# Mxxx.net
KiCad netlist of a schematic drawn in EAGLE
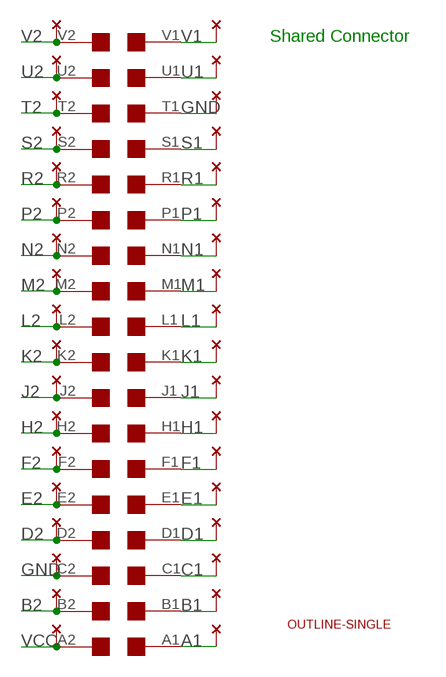
[diagram p0: schematic, sheet 1]
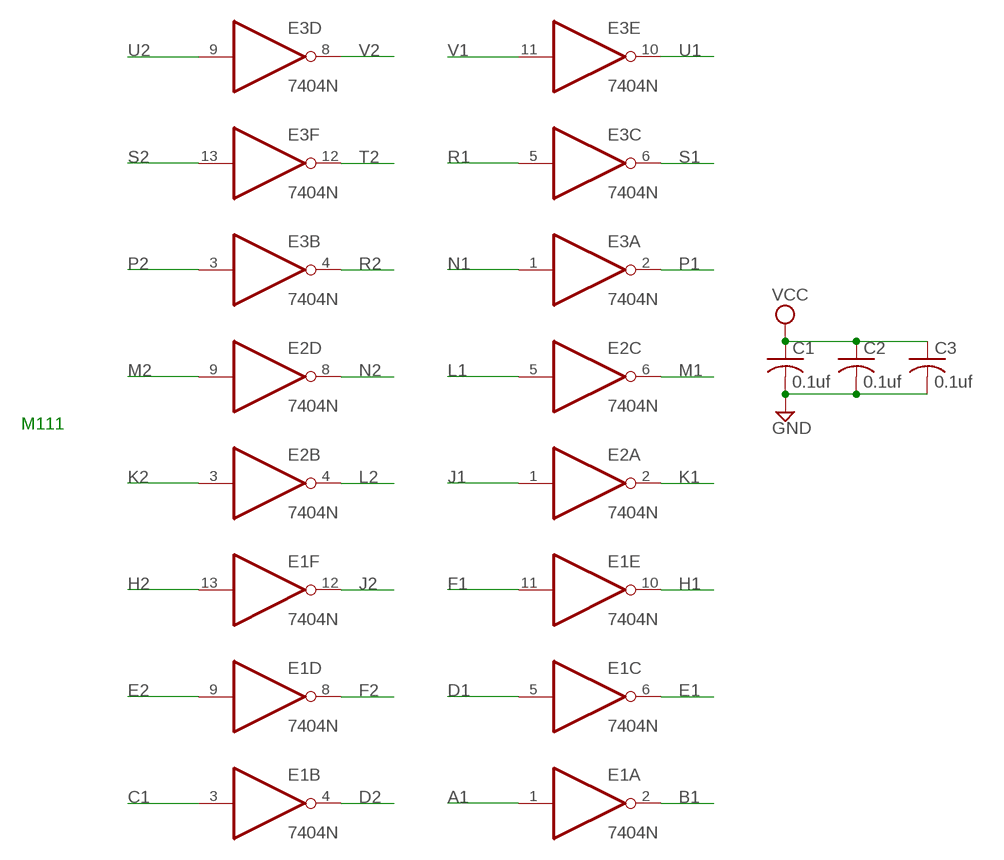
[diagram p1: schematic, sheet 2]
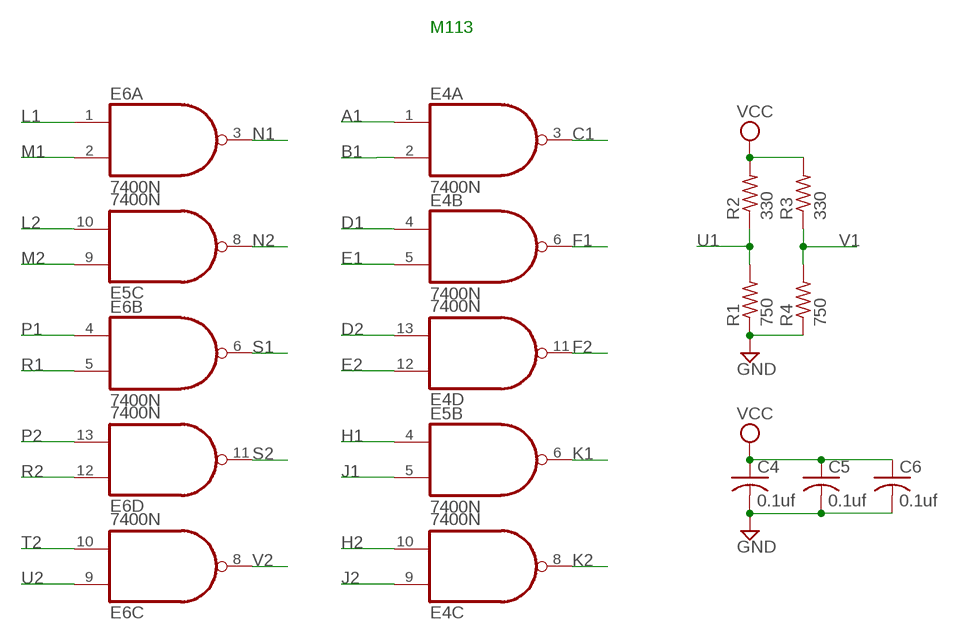
[diagram p2: schematic, sheet 3]
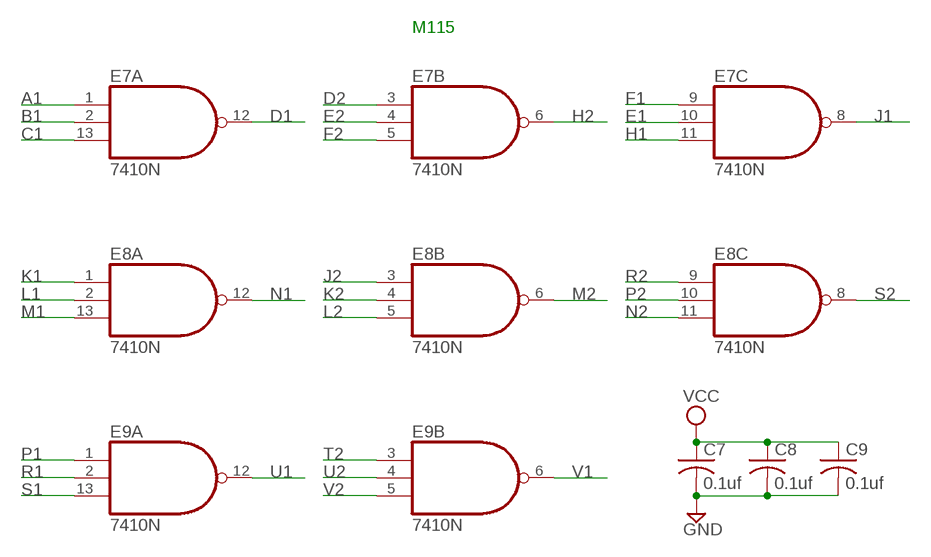
[diagram p3: schematic, sheet 4]
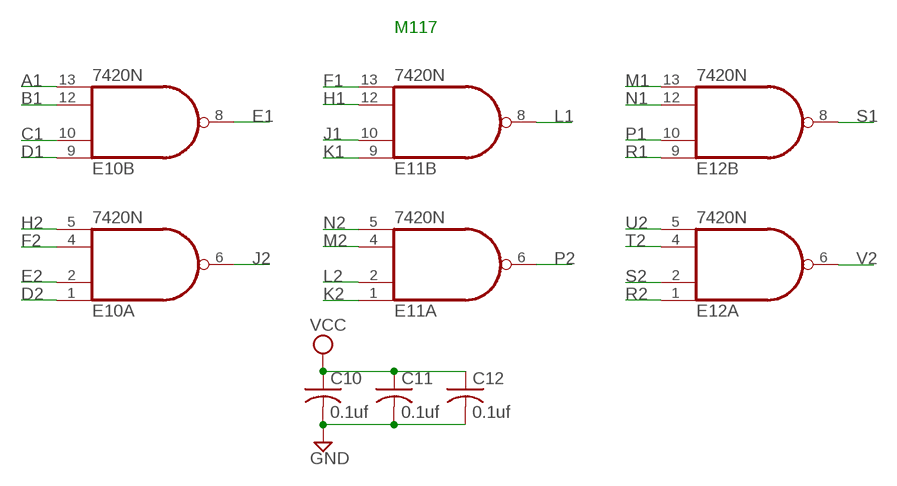
[diagram p4: schematic, sheet 5]
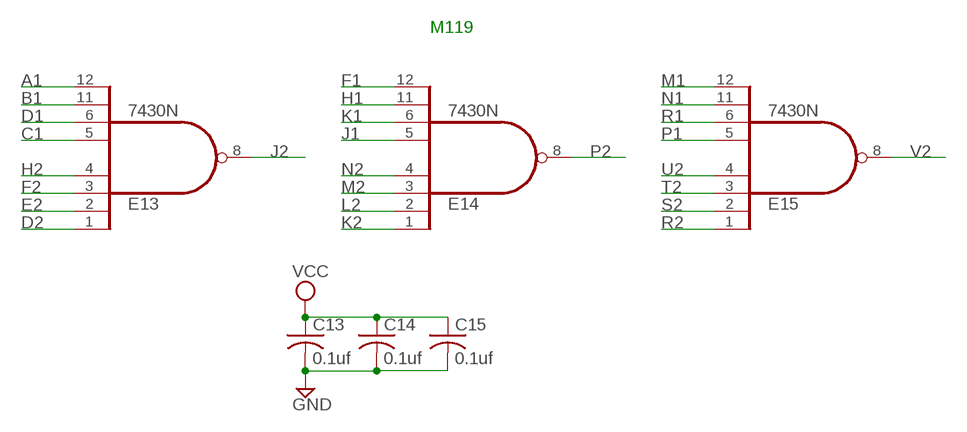
[diagram p5: schematic, sheet 6]

(export (version "E")
  (design (tool "Eeschema 10.0.6"))
  (components
    (comp (ref "C1")
      (value "0.1uf")
      (footprint "eagle-import:C050-025X075")
      (libsource (lib "eagle-import") (part "C-US050-025X075"))
    )
    (comp (ref "C2")
      (value "0.1uf")
      (footprint "eagle-import:C050-025X075")
      (libsource (lib "eagle-import") (part "C-US050-025X075"))
    )
    (comp (ref "C3")
      (value "0.1uf")
      (footprint "eagle-import:C050-025X075")
      (libsource (lib "eagle-import") (part "C-US050-025X075"))
    )
    (comp (ref "E1")
      (value "7404N")
      (footprint "eagle-import:DIL14")
      (libsource (lib "eagle-import") (part "7404N"))
    )
    (comp (ref "E2")
      (value "7404N")
      (footprint "eagle-import:DIL14")
      (libsource (lib "eagle-import") (part "7404N"))
    )
    (comp (ref "E3")
      (value "7404N")
      (footprint "eagle-import:DIL14")
      (libsource (lib "eagle-import") (part "7404N"))
    )
    (comp (ref "C13")
      (value "0.1uf")
      (footprint "eagle-import:C050-025X075")
      (libsource (lib "eagle-import") (part "C-US050-025X075"))
    )
    (comp (ref "C14")
      (value "0.1uf")
      (footprint "eagle-import:C050-025X075")
      (libsource (lib "eagle-import") (part "C-US050-025X075"))
    )
    (comp (ref "C15")
      (value "0.1uf")
      (footprint "eagle-import:C050-025X075")
      (libsource (lib "eagle-import") (part "C-US050-025X075"))
    )
    (comp (ref "E13")
      (value "7430N")
      (footprint "eagle-import:DIL14")
      (libsource (lib "eagle-import") (part "7430N"))
    )
    (comp (ref "E14")
      (value "7430N")
      (footprint "eagle-import:DIL14")
      (libsource (lib "eagle-import") (part "7430N"))
    )
    (comp (ref "E15")
      (value "7430N")
      (footprint "eagle-import:DIL14")
      (libsource (lib "eagle-import") (part "7430N"))
    )
    (comp (ref "C7")
      (value "0.1uf")
      (footprint "eagle-import:C050-025X075")
      (libsource (lib "eagle-import") (part "C-US050-025X075"))
    )
    (comp (ref "C8")
      (value "0.1uf")
      (footprint "eagle-import:C050-025X075")
      (libsource (lib "eagle-import") (part "C-US050-025X075"))
    )
    (comp (ref "C9")
      (value "0.1uf")
      (footprint "eagle-import:C050-025X075")
      (libsource (lib "eagle-import") (part "C-US050-025X075"))
    )
    (comp (ref "E7")
      (value "7410N")
      (footprint "eagle-import:DIL14")
      (libsource (lib "eagle-import") (part "7410N"))
    )
    (comp (ref "E8")
      (value "7410N")
      (footprint "eagle-import:DIL14")
      (libsource (lib "eagle-import") (part "7410N"))
    )
    (comp (ref "E9")
      (value "7410N")
      (footprint "eagle-import:DIL14")
      (libsource (lib "eagle-import") (part "7410N"))
    )
    (comp (ref "C4")
      (value "0.1uf")
      (footprint "eagle-import:C050-025X075")
      (libsource (lib "eagle-import") (part "C-US050-025X075"))
    )
    (comp (ref "C5")
      (value "0.1uf")
      (footprint "eagle-import:C050-025X075")
      (libsource (lib "eagle-import") (part "C-US050-025X075"))
    )
    (comp (ref "C6")
      (value "0.1uf")
      (footprint "eagle-import:C050-025X075")
      (libsource (lib "eagle-import") (part "C-US050-025X075"))
    )
    (comp (ref "E4")
      (value "7400N")
      (footprint "eagle-import:DIL14")
      (libsource (lib "eagle-import") (part "7400N"))
    )
    (comp (ref "E5")
      (value "7400N")
      (footprint "eagle-import:DIL14")
      (libsource (lib "eagle-import") (part "7400N"))
    )
    (comp (ref "E6")
      (value "7400N")
      (footprint "eagle-import:DIL14")
      (libsource (lib "eagle-import") (part "7400N"))
    )
    (comp (ref "R1")
      (value "750")
      (footprint "eagle-import:0207_10")
      (libsource (lib "eagle-import") (part "R-US_0207/10"))
    )
    (comp (ref "R2")
      (value "330")
      (footprint "eagle-import:0207_10")
      (libsource (lib "eagle-import") (part "R-US_0207/10"))
    )
    (comp (ref "R3")
      (value "330")
      (footprint "eagle-import:0207_10")
      (libsource (lib "eagle-import") (part "R-US_0207/10"))
    )
    (comp (ref "R4")
      (value "750")
      (footprint "eagle-import:0207_10")
      (libsource (lib "eagle-import") (part "R-US_0207/10"))
    )
    (comp (ref "C10")
      (value "0.1uf")
      (footprint "eagle-import:C050-025X075")
      (libsource (lib "eagle-import") (part "C-US050-025X075"))
    )
    (comp (ref "C11")
      (value "0.1uf")
      (footprint "eagle-import:C050-025X075")
      (libsource (lib "eagle-import") (part "C-US050-025X075"))
    )
    (comp (ref "C12")
      (value "0.1uf")
      (footprint "eagle-import:C050-025X075")
      (libsource (lib "eagle-import") (part "C-US050-025X075"))
    )
    (comp (ref "E10")
      (value "7420N")
      (footprint "eagle-import:DIL14")
      (libsource (lib "eagle-import") (part "7420NS"))
    )
    (comp (ref "E11")
      (value "7420N")
      (footprint "eagle-import:DIL14")
      (libsource (lib "eagle-import") (part "7420NS"))
    )
    (comp (ref "E12")
      (value "7420N")
      (footprint "eagle-import:DIL14")
      (libsource (lib "eagle-import") (part "7420NS"))
    )
    (comp (ref "U$1")
      (value "EDGE-2CONNECTOR")
      (footprint "eagle-import:EDGE-CON2")
      (libsource (lib "eagle-import") (part "EDGE-2CONNECTOR"))
    )
    (comp (ref "U$4")
      (value "THRU-HOLE2A")
      (footprint "eagle-import:THRU-HOLEA")
      (libsource (lib "eagle-import") (part "THRU-HOLE2A"))
    )
    (comp (ref "U$5")
      (value "OUTLINE-SINGLE")
      (footprint "eagle-import:SINGLE")
      (libsource (lib "eagle-import") (part "OUTLINE-SINGLE"))
    )
  )
  (nets
    (net (code "1") (name "A1") (class "Default")
      (node (ref "E1") (pin "1") (pinfunction "I_1") (pintype "input"))
      (node (ref "E10") (pin "13") (pinfunction "I3_13") (pintype "input"))
      (node (ref "E13") (pin "12") (pinfunction "I7_12") (pintype "input"))
      (node (ref "E4") (pin "1") (pinfunction "I0_1") (pintype "input"))
      (node (ref "E7") (pin "1") (pinfunction "I0_1") (pintype "input"))
      (node (ref "U$1") (pin "A1") (pinfunction "1_A1") (pintype "bidirectional"))
      (node (ref "U$4") (pin "A1") (pinfunction "P$1_A1") (pintype "passive"))
    )
    (net (code "2") (name "B1") (class "Default")
      (node (ref "E1") (pin "2") (pinfunction "O_2") (pintype "output"))
      (node (ref "E10") (pin "12") (pinfunction "I2_12") (pintype "input"))
      (node (ref "E13") (pin "11") (pinfunction "I6_11") (pintype "input"))
      (node (ref "E4") (pin "2") (pinfunction "I1_2") (pintype "input"))
      (node (ref "E7") (pin "2") (pinfunction "I1_2") (pintype "input"))
      (node (ref "U$1") (pin "B1") (pinfunction "1_B1") (pintype "bidirectional"))
      (node (ref "U$4") (pin "B1") (pinfunction "P$1_B1") (pintype "passive"))
    )
    (net (code "3") (name "B2") (class "Default")
      (node (ref "U$1") (pin "B2") (pinfunction "1_B2") (pintype "bidirectional"))
      (node (ref "U$4") (pin "B2") (pinfunction "P$1_B2") (pintype "passive"))
    )
    (net (code "4") (name "C1") (class "Default")
      (node (ref "E1") (pin "3") (pinfunction "I_3") (pintype "input"))
      (node (ref "E10") (pin "10") (pinfunction "I1_10") (pintype "input"))
      (node (ref "E13") (pin "5") (pinfunction "I4_5") (pintype "input"))
      (node (ref "E4") (pin "3") (pinfunction "O_3") (pintype "output"))
      (node (ref "E7") (pin "13") (pinfunction "I2_13") (pintype "input"))
      (node (ref "U$1") (pin "C1") (pinfunction "1_C1") (pintype "bidirectional"))
      (node (ref "U$4") (pin "C1") (pinfunction "P$1_C1") (pintype "passive"))
    )
    (net (code "5") (name "D1") (class "Default")
      (node (ref "E1") (pin "5") (pinfunction "I_5") (pintype "input"))
      (node (ref "E10") (pin "9") (pinfunction "I0_9") (pintype "input"))
      (node (ref "E13") (pin "6") (pinfunction "I5_6") (pintype "input"))
      (node (ref "E4") (pin "4") (pinfunction "I0_4") (pintype "input"))
      (node (ref "E7") (pin "12") (pinfunction "O_12") (pintype "output"))
      (node (ref "U$1") (pin "D1") (pinfunction "1_D1") (pintype "bidirectional"))
      (node (ref "U$4") (pin "D1") (pinfunction "P$1_D1") (pintype "passive"))
    )
    (net (code "6") (name "D2") (class "Default")
      (node (ref "E1") (pin "4") (pinfunction "O_4") (pintype "output"))
      (node (ref "E10") (pin "1") (pinfunction "I0_1") (pintype "input"))
      (node (ref "E13") (pin "1") (pinfunction "I0_1") (pintype "input"))
      (node (ref "E4") (pin "13") (pinfunction "I1_13") (pintype "input"))
      (node (ref "E7") (pin "3") (pinfunction "I0_3") (pintype "input"))
      (node (ref "U$1") (pin "D2") (pinfunction "1_D2") (pintype "bidirectional"))
      (node (ref "U$4") (pin "D2") (pinfunction "P$1_D2") (pintype "passive"))
    )
    (net (code "7") (name "E1") (class "Default")
      (node (ref "E1") (pin "6") (pinfunction "O_6") (pintype "output"))
      (node (ref "E10") (pin "8") (pinfunction "O_8") (pintype "output"))
      (node (ref "E4") (pin "5") (pinfunction "I1_5") (pintype "input"))
      (node (ref "E7") (pin "10") (pinfunction "I1_10") (pintype "input"))
      (node (ref "U$1") (pin "E1") (pinfunction "1_E1") (pintype "bidirectional"))
      (node (ref "U$4") (pin "E1") (pinfunction "P$1_E1") (pintype "passive"))
    )
    (net (code "8") (name "E2") (class "Default")
      (node (ref "E1") (pin "9") (pinfunction "I_9") (pintype "input"))
      (node (ref "E10") (pin "2") (pinfunction "I1_2") (pintype "input"))
      (node (ref "E13") (pin "2") (pinfunction "I1_2") (pintype "input"))
      (node (ref "E4") (pin "12") (pinfunction "I0_12") (pintype "input"))
      (node (ref "E7") (pin "4") (pinfunction "I1_4") (pintype "input"))
      (node (ref "U$1") (pin "E2") (pinfunction "1_E2") (pintype "bidirectional"))
      (node (ref "U$4") (pin "E2") (pinfunction "P$1_E2") (pintype "passive"))
    )
    (net (code "9") (name "F1") (class "Default")
      (node (ref "E1") (pin "11") (pinfunction "I_11") (pintype "input"))
      (node (ref "E11") (pin "13") (pinfunction "I3_13") (pintype "input"))
      (node (ref "E14") (pin "12") (pinfunction "I7_12") (pintype "input"))
      (node (ref "E4") (pin "6") (pinfunction "O_6") (pintype "output"))
      (node (ref "E7") (pin "9") (pinfunction "I0_9") (pintype "input"))
      (node (ref "U$1") (pin "F1") (pinfunction "1_F1") (pintype "bidirectional"))
      (node (ref "U$4") (pin "F1") (pinfunction "P$1_F1") (pintype "passive"))
    )
    (net (code "10") (name "F2") (class "Default")
      (node (ref "E1") (pin "8") (pinfunction "O_8") (pintype "output"))
      (node (ref "E10") (pin "4") (pinfunction "I2_4") (pintype "input"))
      (node (ref "E13") (pin "3") (pinfunction "I2_3") (pintype "input"))
      (node (ref "E4") (pin "11") (pinfunction "O_11") (pintype "output"))
      (node (ref "E7") (pin "5") (pinfunction "I2_5") (pintype "input"))
      (node (ref "U$1") (pin "F2") (pinfunction "1_F2") (pintype "bidirectional"))
      (node (ref "U$4") (pin "F2") (pinfunction "P$1_F2") (pintype "passive"))
    )
    (net (code "11") (name "GND") (class "Default")
      (node (ref "C1") (pin "2") (pinfunction "2_2") (pintype "passive"))
      (node (ref "C10") (pin "2") (pinfunction "2_2") (pintype "passive"))
      (node (ref "C11") (pin "2") (pinfunction "2_2") (pintype "passive"))
      (node (ref "C12") (pin "2") (pinfunction "2_2") (pintype "passive"))
      (node (ref "C13") (pin "2") (pinfunction "2_2") (pintype "passive"))
      (node (ref "C14") (pin "2") (pinfunction "2_2") (pintype "passive"))
      (node (ref "C15") (pin "2") (pinfunction "2_2") (pintype "passive"))
      (node (ref "C2") (pin "2") (pinfunction "2_2") (pintype "passive"))
      (node (ref "C3") (pin "2") (pinfunction "2_2") (pintype "passive"))
      (node (ref "C4") (pin "2") (pinfunction "2_2") (pintype "passive"))
      (node (ref "C5") (pin "2") (pinfunction "2_2") (pintype "passive"))
      (node (ref "C6") (pin "2") (pinfunction "2_2") (pintype "passive"))
      (node (ref "C7") (pin "2") (pinfunction "2_2") (pintype "passive"))
      (node (ref "C8") (pin "2") (pinfunction "2_2") (pintype "passive"))
      (node (ref "C9") (pin "2") (pinfunction "2_2") (pintype "passive"))
      (node (ref "R1") (pin "1") (pinfunction "1_1") (pintype "passive"))
      (node (ref "R4") (pin "1") (pinfunction "1_1") (pintype "passive"))
      (node (ref "U$1") (pin "C2") (pinfunction "1_C2") (pintype "bidirectional"))
      (node (ref "U$1") (pin "T1") (pinfunction "1_T1") (pintype "bidirectional"))
      (node (ref "U$4") (pin "C2") (pinfunction "P$1_C2") (pintype "passive"))
      (node (ref "U$4") (pin "T1") (pinfunction "P$1_T1") (pintype "passive"))
    )
    (net (code "12") (name "H1") (class "Default")
      (node (ref "E1") (pin "10") (pinfunction "O_10") (pintype "output"))
      (node (ref "E11") (pin "12") (pinfunction "I2_12") (pintype "input"))
      (node (ref "E14") (pin "11") (pinfunction "I6_11") (pintype "input"))
      (node (ref "E5") (pin "4") (pinfunction "I0_4") (pintype "input"))
      (node (ref "E7") (pin "11") (pinfunction "I2_11") (pintype "input"))
      (node (ref "U$1") (pin "H1") (pinfunction "1_H1") (pintype "bidirectional"))
      (node (ref "U$4") (pin "H1") (pinfunction "P$1_H1") (pintype "passive"))
    )
    (net (code "13") (name "H2") (class "Default")
      (node (ref "E1") (pin "13") (pinfunction "I_13") (pintype "input"))
      (node (ref "E10") (pin "5") (pinfunction "I3_5") (pintype "input"))
      (node (ref "E13") (pin "4") (pinfunction "I3_4") (pintype "input"))
      (node (ref "E4") (pin "10") (pinfunction "I1_10") (pintype "input"))
      (node (ref "E7") (pin "6") (pinfunction "O_6") (pintype "output"))
      (node (ref "U$1") (pin "H2") (pinfunction "1_H2") (pintype "bidirectional"))
      (node (ref "U$4") (pin "H2") (pinfunction "P$1_H2") (pintype "passive"))
    )
    (net (code "14") (name "J1") (class "Default")
      (node (ref "E11") (pin "10") (pinfunction "I1_10") (pintype "input"))
      (node (ref "E14") (pin "5") (pinfunction "I4_5") (pintype "input"))
      (node (ref "E2") (pin "1") (pinfunction "I_1") (pintype "input"))
      (node (ref "E5") (pin "5") (pinfunction "I1_5") (pintype "input"))
      (node (ref "E7") (pin "8") (pinfunction "O_8") (pintype "output"))
      (node (ref "U$1") (pin "J1") (pinfunction "1_J1") (pintype "bidirectional"))
      (node (ref "U$4") (pin "J1") (pinfunction "P$1_J1") (pintype "passive"))
    )
    (net (code "15") (name "J2") (class "Default")
      (node (ref "E1") (pin "12") (pinfunction "O_12") (pintype "output"))
      (node (ref "E10") (pin "6") (pinfunction "O_6") (pintype "output"))
      (node (ref "E13") (pin "8") (pinfunction "O_8") (pintype "output"))
      (node (ref "E4") (pin "9") (pinfunction "I0_9") (pintype "input"))
      (node (ref "E8") (pin "3") (pinfunction "I0_3") (pintype "input"))
      (node (ref "U$1") (pin "J2") (pinfunction "1_J2") (pintype "bidirectional"))
      (node (ref "U$4") (pin "J2") (pinfunction "P$1_J2") (pintype "passive"))
    )
    (net (code "16") (name "K1") (class "Default")
      (node (ref "E11") (pin "9") (pinfunction "I0_9") (pintype "input"))
      (node (ref "E14") (pin "6") (pinfunction "I5_6") (pintype "input"))
      (node (ref "E2") (pin "2") (pinfunction "O_2") (pintype "output"))
      (node (ref "E5") (pin "6") (pinfunction "O_6") (pintype "output"))
      (node (ref "E8") (pin "1") (pinfunction "I0_1") (pintype "input"))
      (node (ref "U$1") (pin "K1") (pinfunction "1_K1") (pintype "bidirectional"))
      (node (ref "U$4") (pin "K1") (pinfunction "P$1_K1") (pintype "passive"))
    )
    (net (code "17") (name "K2") (class "Default")
      (node (ref "E11") (pin "1") (pinfunction "I0_1") (pintype "input"))
      (node (ref "E14") (pin "1") (pinfunction "I0_1") (pintype "input"))
      (node (ref "E2") (pin "3") (pinfunction "I_3") (pintype "input"))
      (node (ref "E4") (pin "8") (pinfunction "O_8") (pintype "output"))
      (node (ref "E8") (pin "4") (pinfunction "I1_4") (pintype "input"))
      (node (ref "U$1") (pin "K2") (pinfunction "1_K2") (pintype "bidirectional"))
      (node (ref "U$4") (pin "K2") (pinfunction "P$1_K2") (pintype "passive"))
    )
    (net (code "18") (name "L1") (class "Default")
      (node (ref "E11") (pin "8") (pinfunction "O_8") (pintype "output"))
      (node (ref "E2") (pin "5") (pinfunction "I_5") (pintype "input"))
      (node (ref "E6") (pin "1") (pinfunction "I0_1") (pintype "input"))
      (node (ref "E8") (pin "2") (pinfunction "I1_2") (pintype "input"))
      (node (ref "U$1") (pin "L1") (pinfunction "1_L1") (pintype "bidirectional"))
      (node (ref "U$4") (pin "L1") (pinfunction "P$1_L1") (pintype "passive"))
    )
    (net (code "19") (name "L2") (class "Default")
      (node (ref "E11") (pin "2") (pinfunction "I1_2") (pintype "input"))
      (node (ref "E14") (pin "2") (pinfunction "I1_2") (pintype "input"))
      (node (ref "E2") (pin "4") (pinfunction "O_4") (pintype "output"))
      (node (ref "E5") (pin "10") (pinfunction "I1_10") (pintype "input"))
      (node (ref "E8") (pin "5") (pinfunction "I2_5") (pintype "input"))
      (node (ref "U$1") (pin "L2") (pinfunction "1_L2") (pintype "bidirectional"))
      (node (ref "U$4") (pin "L2") (pinfunction "P$1_L2") (pintype "passive"))
    )
    (net (code "20") (name "M1") (class "Default")
      (node (ref "E12") (pin "13") (pinfunction "I3_13") (pintype "input"))
      (node (ref "E15") (pin "12") (pinfunction "I7_12") (pintype "input"))
      (node (ref "E2") (pin "6") (pinfunction "O_6") (pintype "output"))
      (node (ref "E6") (pin "2") (pinfunction "I1_2") (pintype "input"))
      (node (ref "E8") (pin "13") (pinfunction "I2_13") (pintype "input"))
      (node (ref "U$1") (pin "M1") (pinfunction "1_M1") (pintype "bidirectional"))
      (node (ref "U$4") (pin "M1") (pinfunction "P$1_M1") (pintype "passive"))
    )
    (net (code "21") (name "M2") (class "Default")
      (node (ref "E11") (pin "4") (pinfunction "I2_4") (pintype "input"))
      (node (ref "E14") (pin "3") (pinfunction "I2_3") (pintype "input"))
      (node (ref "E2") (pin "9") (pinfunction "I_9") (pintype "input"))
      (node (ref "E5") (pin "9") (pinfunction "I0_9") (pintype "input"))
      (node (ref "E8") (pin "6") (pinfunction "O_6") (pintype "output"))
      (node (ref "U$1") (pin "M2") (pinfunction "1_M2") (pintype "bidirectional"))
      (node (ref "U$4") (pin "M2") (pinfunction "P$1_M2") (pintype "passive"))
    )
    (net (code "22") (name "N1") (class "Default")
      (node (ref "E12") (pin "12") (pinfunction "I2_12") (pintype "input"))
      (node (ref "E15") (pin "11") (pinfunction "I6_11") (pintype "input"))
      (node (ref "E3") (pin "1") (pinfunction "I_1") (pintype "input"))
      (node (ref "E6") (pin "3") (pinfunction "O_3") (pintype "output"))
      (node (ref "E8") (pin "12") (pinfunction "O_12") (pintype "output"))
      (node (ref "U$1") (pin "N1") (pinfunction "1_N1") (pintype "bidirectional"))
      (node (ref "U$4") (pin "N1") (pinfunction "P$1_N1") (pintype "passive"))
    )
    (net (code "23") (name "N2") (class "Default")
      (node (ref "E11") (pin "5") (pinfunction "I3_5") (pintype "input"))
      (node (ref "E14") (pin "4") (pinfunction "I3_4") (pintype "input"))
      (node (ref "E2") (pin "8") (pinfunction "O_8") (pintype "output"))
      (node (ref "E5") (pin "8") (pinfunction "O_8") (pintype "output"))
      (node (ref "E8") (pin "11") (pinfunction "I2_11") (pintype "input"))
      (node (ref "U$1") (pin "N2") (pinfunction "1_N2") (pintype "bidirectional"))
      (node (ref "U$4") (pin "N2") (pinfunction "P$1_N2") (pintype "passive"))
    )
    (net (code "24") (name "P1") (class "Default")
      (node (ref "E12") (pin "10") (pinfunction "I1_10") (pintype "input"))
      (node (ref "E15") (pin "5") (pinfunction "I4_5") (pintype "input"))
      (node (ref "E3") (pin "2") (pinfunction "O_2") (pintype "output"))
      (node (ref "E6") (pin "4") (pinfunction "I0_4") (pintype "input"))
      (node (ref "E9") (pin "1") (pinfunction "I0_1") (pintype "input"))
      (node (ref "U$1") (pin "P1") (pinfunction "1_P1") (pintype "bidirectional"))
      (node (ref "U$4") (pin "P1") (pinfunction "P$1_P1") (pintype "passive"))
    )
    (net (code "25") (name "P2") (class "Default")
      (node (ref "E11") (pin "6") (pinfunction "O_6") (pintype "output"))
      (node (ref "E14") (pin "8") (pinfunction "O_8") (pintype "output"))
      (node (ref "E3") (pin "3") (pinfunction "I_3") (pintype "input"))
      (node (ref "E6") (pin "13") (pinfunction "I1_13") (pintype "input"))
      (node (ref "E8") (pin "10") (pinfunction "I1_10") (pintype "input"))
      (node (ref "U$1") (pin "P2") (pinfunction "1_P2") (pintype "bidirectional"))
      (node (ref "U$4") (pin "P2") (pinfunction "P$1_P2") (pintype "passive"))
    )
    (net (code "26") (name "R1") (class "Default")
      (node (ref "E12") (pin "9") (pinfunction "I0_9") (pintype "input"))
      (node (ref "E15") (pin "6") (pinfunction "I5_6") (pintype "input"))
      (node (ref "E3") (pin "5") (pinfunction "I_5") (pintype "input"))
      (node (ref "E6") (pin "5") (pinfunction "I1_5") (pintype "input"))
      (node (ref "E9") (pin "2") (pinfunction "I1_2") (pintype "input"))
      (node (ref "U$1") (pin "R1") (pinfunction "1_R1") (pintype "bidirectional"))
      (node (ref "U$4") (pin "R1") (pinfunction "P$1_R1") (pintype "passive"))
    )
    (net (code "27") (name "R2") (class "Default")
      (node (ref "E12") (pin "1") (pinfunction "I0_1") (pintype "input"))
      (node (ref "E15") (pin "1") (pinfunction "I0_1") (pintype "input"))
      (node (ref "E3") (pin "4") (pinfunction "O_4") (pintype "output"))
      (node (ref "E6") (pin "12") (pinfunction "I0_12") (pintype "input"))
      (node (ref "E8") (pin "9") (pinfunction "I0_9") (pintype "input"))
      (node (ref "U$1") (pin "R2") (pinfunction "1_R2") (pintype "bidirectional"))
      (node (ref "U$4") (pin "R2") (pinfunction "P$1_R2") (pintype "passive"))
    )
    (net (code "28") (name "S1") (class "Default")
      (node (ref "E12") (pin "8") (pinfunction "O_8") (pintype "output"))
      (node (ref "E3") (pin "6") (pinfunction "O_6") (pintype "output"))
      (node (ref "E6") (pin "6") (pinfunction "O_6") (pintype "output"))
      (node (ref "E9") (pin "13") (pinfunction "I2_13") (pintype "input"))
      (node (ref "U$1") (pin "S1") (pinfunction "1_S1") (pintype "bidirectional"))
      (node (ref "U$4") (pin "S2") (pinfunction "P$1_S2") (pintype "passive"))
    )
    (net (code "29") (name "S2") (class "Default")
      (node (ref "E12") (pin "2") (pinfunction "I1_2") (pintype "input"))
      (node (ref "E15") (pin "2") (pinfunction "I1_2") (pintype "input"))
      (node (ref "E3") (pin "13") (pinfunction "I_13") (pintype "input"))
      (node (ref "E6") (pin "11") (pinfunction "O_11") (pintype "output"))
      (node (ref "E8") (pin "8") (pinfunction "O_8") (pintype "output"))
      (node (ref "U$1") (pin "S2") (pinfunction "1_S2") (pintype "bidirectional"))
      (node (ref "U$4") (pin "S1") (pinfunction "P$1_S1") (pintype "passive"))
    )
    (net (code "30") (name "T2") (class "Default")
      (node (ref "E12") (pin "4") (pinfunction "I2_4") (pintype "input"))
      (node (ref "E15") (pin "3") (pinfunction "I2_3") (pintype "input"))
      (node (ref "E3") (pin "12") (pinfunction "O_12") (pintype "output"))
      (node (ref "E6") (pin "10") (pinfunction "I1_10") (pintype "input"))
      (node (ref "E9") (pin "3") (pinfunction "I0_3") (pintype "input"))
      (node (ref "U$1") (pin "T2") (pinfunction "1_T2") (pintype "bidirectional"))
      (node (ref "U$4") (pin "T2") (pinfunction "P$1_T2") (pintype "passive"))
    )
    (net (code "31") (name "U1") (class "Default")
      (node (ref "E3") (pin "10") (pinfunction "O_10") (pintype "output"))
      (node (ref "E9") (pin "12") (pinfunction "O_12") (pintype "output"))
      (node (ref "R1") (pin "2") (pinfunction "2_2") (pintype "passive"))
      (node (ref "R2") (pin "1") (pinfunction "1_1") (pintype "passive"))
      (node (ref "U$1") (pin "U1") (pinfunction "1_U1") (pintype "bidirectional"))
      (node (ref "U$4") (pin "U1") (pinfunction "P$1_U1") (pintype "passive"))
    )
    (net (code "32") (name "U2") (class "Default")
      (node (ref "E12") (pin "5") (pinfunction "I3_5") (pintype "input"))
      (node (ref "E15") (pin "4") (pinfunction "I3_4") (pintype "input"))
      (node (ref "E3") (pin "9") (pinfunction "I_9") (pintype "input"))
      (node (ref "E6") (pin "9") (pinfunction "I0_9") (pintype "input"))
      (node (ref "E9") (pin "4") (pinfunction "I1_4") (pintype "input"))
      (node (ref "U$1") (pin "U2") (pinfunction "1_U2") (pintype "bidirectional"))
      (node (ref "U$4") (pin "U2") (pinfunction "P$1_U2") (pintype "passive"))
    )
    (net (code "33") (name "V1") (class "Default")
      (node (ref "E3") (pin "11") (pinfunction "I_11") (pintype "input"))
      (node (ref "E9") (pin "6") (pinfunction "O_6") (pintype "output"))
      (node (ref "R3") (pin "1") (pinfunction "1_1") (pintype "passive"))
      (node (ref "R4") (pin "2") (pinfunction "2_2") (pintype "passive"))
      (node (ref "U$1") (pin "V1") (pinfunction "1_V1") (pintype "bidirectional"))
      (node (ref "U$4") (pin "V1") (pinfunction "P$1_V1") (pintype "passive"))
    )
    (net (code "34") (name "V2") (class "Default")
      (node (ref "E12") (pin "6") (pinfunction "O_6") (pintype "output"))
      (node (ref "E15") (pin "8") (pinfunction "O_8") (pintype "output"))
      (node (ref "E3") (pin "8") (pinfunction "O_8") (pintype "output"))
      (node (ref "E6") (pin "8") (pinfunction "O_8") (pintype "output"))
      (node (ref "E9") (pin "5") (pinfunction "I2_5") (pintype "input"))
      (node (ref "U$1") (pin "V2") (pinfunction "1_V2") (pintype "bidirectional"))
      (node (ref "U$4") (pin "V2") (pinfunction "P$1_V2") (pintype "passive"))
    )
    (net (code "35") (name "VCC") (class "Default")
      (node (ref "C1") (pin "1") (pinfunction "1_1") (pintype "passive"))
      (node (ref "C10") (pin "1") (pinfunction "1_1") (pintype "passive"))
      (node (ref "C11") (pin "1") (pinfunction "1_1") (pintype "passive"))
      (node (ref "C12") (pin "1") (pinfunction "1_1") (pintype "passive"))
      (node (ref "C13") (pin "1") (pinfunction "1_1") (pintype "passive"))
      (node (ref "C14") (pin "1") (pinfunction "1_1") (pintype "passive"))
      (node (ref "C15") (pin "1") (pinfunction "1_1") (pintype "passive"))
      (node (ref "C2") (pin "1") (pinfunction "1_1") (pintype "passive"))
      (node (ref "C3") (pin "1") (pinfunction "1_1") (pintype "passive"))
      (node (ref "C4") (pin "1") (pinfunction "1_1") (pintype "passive"))
      (node (ref "C5") (pin "1") (pinfunction "1_1") (pintype "passive"))
      (node (ref "C6") (pin "1") (pinfunction "1_1") (pintype "passive"))
      (node (ref "C7") (pin "1") (pinfunction "1_1") (pintype "passive"))
      (node (ref "C8") (pin "1") (pinfunction "1_1") (pintype "passive"))
      (node (ref "C9") (pin "1") (pinfunction "1_1") (pintype "passive"))
      (node (ref "R2") (pin "2") (pinfunction "2_2") (pintype "passive"))
      (node (ref "R3") (pin "2") (pinfunction "2_2") (pintype "passive"))
      (node (ref "U$1") (pin "A2") (pinfunction "1_A2") (pintype "bidirectional"))
      (node (ref "U$4") (pin "A2") (pinfunction "P$1_A2") (pintype "passive"))
    )
  )
)
